# p2-001.net
KiCad netlist of a schematic drawn in EAGLE
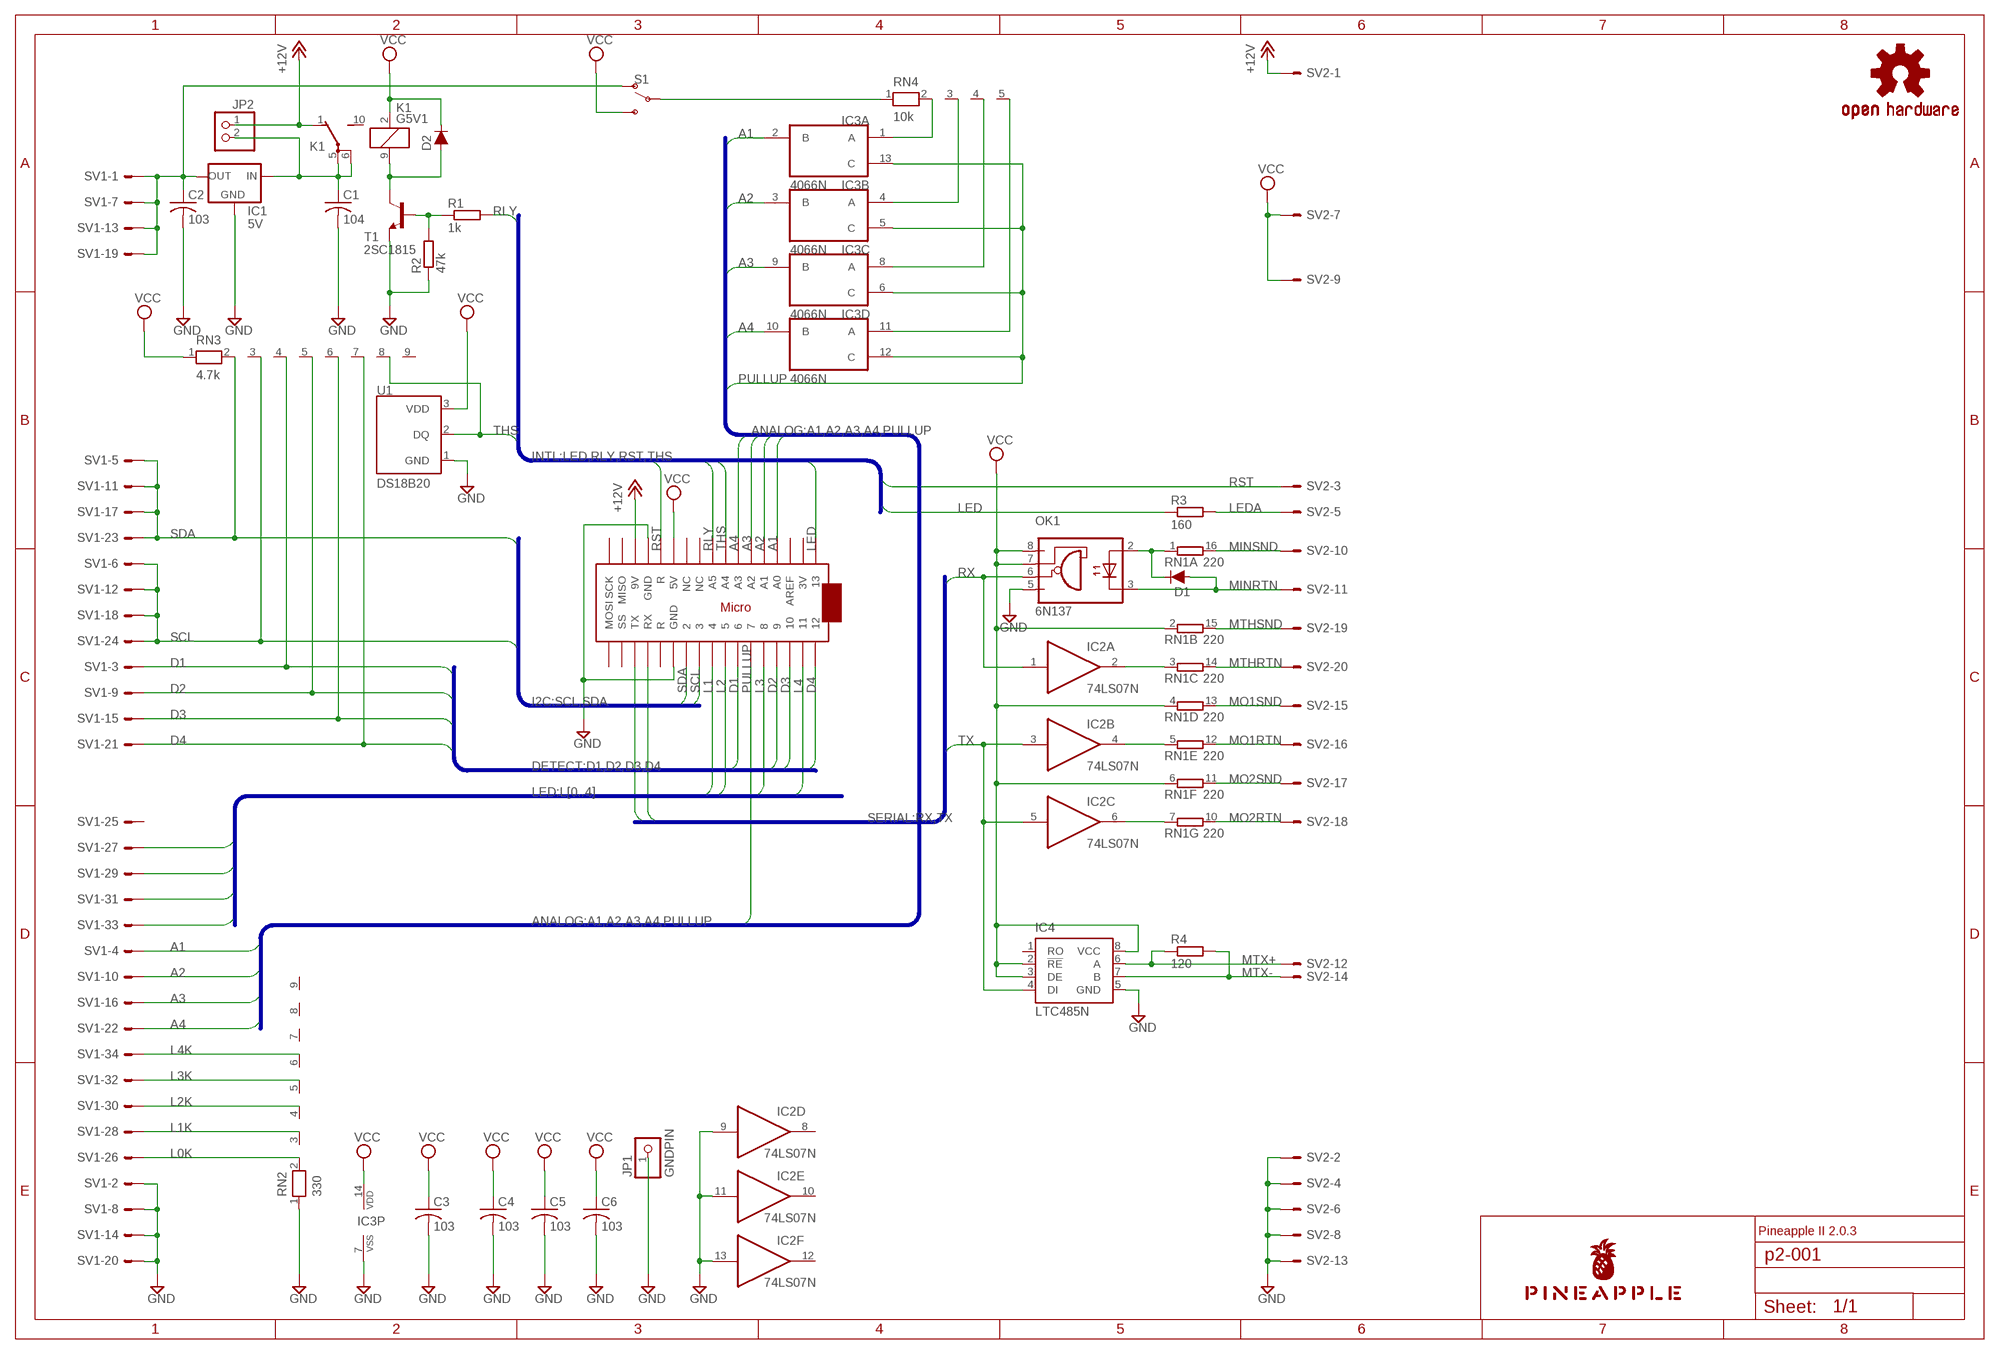
[diagram p0: schematic, sheet 1]

(export (version "E")
  (design (tool "Eeschema 10.0.6"))
  (components
    (comp (ref "C1")
      (value "104")
      (footprint "eagle-import:C025-025X050")
      (libsource (lib "eagle-import") (part "C-US025-025X050"))
    )
    (comp (ref "C2")
      (value "103")
      (footprint "eagle-import:C025-025X050")
      (libsource (lib "eagle-import") (part "C-US025-025X050"))
    )
    (comp (ref "C3")
      (value "103")
      (footprint "eagle-import:C025-025X050")
      (libsource (lib "eagle-import") (part "C-US025-025X050"))
    )
    (comp (ref "C4")
      (value "103")
      (footprint "eagle-import:C025-025X050")
      (libsource (lib "eagle-import") (part "C-US025-025X050"))
    )
    (comp (ref "C5")
      (value "103")
      (footprint "eagle-import:C025-025X050")
      (libsource (lib "eagle-import") (part "C-US025-025X050"))
    )
    (comp (ref "C6")
      (value "103")
      (footprint "eagle-import:C025-025X050")
      (libsource (lib "eagle-import") (part "C-US025-025X050"))
    )
    (comp (ref "D1")
      (value "DIODE-1N4148")
      (footprint "eagle-import:DIODE-1N4148")
      (libsource (lib "eagle-import") (part "DIODE-1N4148"))
    )
    (comp (ref "D2")
      (value "DIODE-1N4148")
      (footprint "eagle-import:DIODE-1N4148")
      (libsource (lib "eagle-import") (part "DIODE-1N4148"))
    )
    (comp (ref "IC1")
      (value "5V")
      (footprint "eagle-import:78XXL")
      (libsource (lib "eagle-import") (part "78XXL"))
    )
    (comp (ref "IC2")
      (value "74LS07N")
      (footprint "eagle-import:DIL14")
      (libsource (lib "eagle-import") (part "7407NLS"))
    )
    (comp (ref "IC3")
      (value "4066N")
      (footprint "eagle-import:DIL14")
      (libsource (lib "eagle-import") (part "4066N"))
    )
    (comp (ref "IC4")
      (value "LTC485N")
      (footprint "eagle-import:DIL08")
      (libsource (lib "eagle-import") (part "LTC485N"))
    )
    (comp (ref "JP1")
      (value "GNDPIN")
      (footprint "eagle-import:1X01")
      (libsource (lib "eagle-import") (part "PINHD-1X1"))
    )
    (comp (ref "JP2")
      (value "PINHD-1X2")
      (footprint "eagle-import:1X02")
      (libsource (lib "eagle-import") (part "PINHD-1X2"))
    )
    (comp (ref "K1")
      (value "G5V1")
      (footprint "eagle-import:G5V1")
      (fields (field (name "MPN") "G5V-1-DC24"))
      (libsource (lib "eagle-import") (part "G5V1"))
    )
    (comp (ref "LOGO1")
      (value "OSHW-LOGOS-COPPER")
      (footprint "eagle-import:OSHW-LOGO-S_COPPER")
      (libsource (lib "eagle-import") (part "OSHW-LOGOS-COPPER"))
    )
    (comp (ref "MC1")
      (value "ARDUINOMICRO")
      (footprint "eagle-import:ARDUINOMICRO")
      (libsource (lib "eagle-import") (part "ARDUINOMICRO"))
    )
    (comp (ref "OK1")
      (value "6N137")
      (footprint "eagle-import:DIL08")
      (libsource (lib "eagle-import") (part "6N137"))
    )
    (comp (ref "R1")
      (value "1k")
      (footprint "eagle-import:0204_5")
      (libsource (lib "eagle-import") (part "R-EU_0204/5"))
    )
    (comp (ref "R2")
      (value "47k")
      (footprint "eagle-import:0204_5")
      (libsource (lib "eagle-import") (part "R-EU_0204/5"))
    )
    (comp (ref "R3")
      (value "160")
      (footprint "eagle-import:0204_5")
      (libsource (lib "eagle-import") (part "R-EU_0204/5"))
    )
    (comp (ref "R4")
      (value "120")
      (footprint "eagle-import:0204_5")
      (libsource (lib "eagle-import") (part "R-EU_0204/5"))
    )
    (comp (ref "RN1")
      (value "220")
      (footprint "eagle-import:DIL16")
      (libsource (lib "eagle-import") (part "8R-N"))
    )
    (comp (ref "RN2")
      (value "330")
      (footprint "eagle-import:RN-9")
      (libsource (lib "eagle-import") (part "RN08"))
    )
    (comp (ref "RN3")
      (value "4.7k")
      (footprint "eagle-import:RN-9")
      (libsource (lib "eagle-import") (part "RN08"))
    )
    (comp (ref "RN4")
      (value "10k")
      (footprint "eagle-import:RN-5")
      (libsource (lib "eagle-import") (part "RN04"))
    )
    (comp (ref "S1")
      (value "SWITCH-SPDT-PTH-11.6X4.0MM")
      (footprint "eagle-import:SWITCH_SPDT_PTH_11.6X4.0MM")
      (libsource (lib "eagle-import") (part "SWITCH-SPDT-PTH-11.6X4.0MM"))
    )
    (comp (ref "SV1")
      (value "ML34LE")
      (footprint "eagle-import:ML34L")
      (libsource (lib "eagle-import") (part "ML34LE"))
    )
    (comp (ref "SV2")
      (value "ML20LE")
      (footprint "eagle-import:ML20L")
      (libsource (lib "eagle-import") (part "ML20LE"))
    )
    (comp (ref "T1")
      (value "2SC1815")
      (footprint "eagle-import:TO92-ECB")
      (libsource (lib "eagle-import") (part "2SC1815"))
    )
    (comp (ref "U$1")
      (value "PINEAPPLE450_SILK")
      (footprint "eagle-import:PINEAPPLE450_SILK")
      (libsource (lib "eagle-import") (part "PINEAPPLE450_SILK"))
    )
    (comp (ref "U1")
      (value "DS18B20")
      (footprint "eagle-import:TO-92-AMMO")
      (libsource (lib "eagle-import") (part "DS18B20"))
    )
  )
  (nets
    (net (code "11") (name "+12V") (class "Default")
      (node (ref "JP2") (pin "1") (pinfunction "1_1") (pintype "passive"))
      (node (ref "K1") (pin "1") (pinfunction "O_1") (pintype "passive"))
      (node (ref "MC1") (pin "P$20") (pinfunction "9V_P$20") (pintype "bidirectional"))
      (node (ref "SV2") (pin "1") (pinfunction "S_1") (pintype "passive"))
    )
    (net (code "12") (name "/A1") (class "Default")
      (node (ref "IC3") (pin "2") (pinfunction "B_2") (pintype "tri_state"))
      (node (ref "MC1") (pin "P$31") (pinfunction "A0_P$31") (pintype "bidirectional"))
      (node (ref "SV1") (pin "4") (pinfunction "S_4") (pintype "passive"))
    )
    (net (code "13") (name "/A2") (class "Default")
      (node (ref "IC3") (pin "3") (pinfunction "B_3") (pintype "tri_state"))
      (node (ref "MC1") (pin "P$30") (pinfunction "A1_P$30") (pintype "bidirectional"))
      (node (ref "SV1") (pin "10") (pinfunction "S_10") (pintype "passive"))
    )
    (net (code "14") (name "/A3") (class "Default")
      (node (ref "IC3") (pin "9") (pinfunction "B_9") (pintype "tri_state"))
      (node (ref "MC1") (pin "P$29") (pinfunction "A2_P$29") (pintype "bidirectional"))
      (node (ref "SV1") (pin "16") (pinfunction "S_16") (pintype "passive"))
    )
    (net (code "15") (name "/A4") (class "Default")
      (node (ref "IC3") (pin "10") (pinfunction "B_10") (pintype "tri_state"))
      (node (ref "MC1") (pin "P$28") (pinfunction "A3_P$28") (pintype "bidirectional"))
      (node (ref "SV1") (pin "22") (pinfunction "S_22") (pintype "passive"))
    )
    (net (code "16") (name "/D1") (class "Default")
      (node (ref "MC1") (pin "P$7") (pinfunction "6_P$7") (pintype "bidirectional"))
      (node (ref "RN3") (pin "4") (pinfunction "4_4") (pintype "passive"))
      (node (ref "SV1") (pin "3") (pinfunction "S_3") (pintype "passive"))
    )
    (net (code "17") (name "/D2") (class "Default")
      (node (ref "MC1") (pin "P$4") (pinfunction "9_P$4") (pintype "bidirectional"))
      (node (ref "RN3") (pin "5") (pinfunction "5_5") (pintype "passive"))
      (node (ref "SV1") (pin "9") (pinfunction "S_9") (pintype "passive"))
    )
    (net (code "18") (name "/D3") (class "Default")
      (node (ref "MC1") (pin "P$3") (pinfunction "10_P$3") (pintype "bidirectional"))
      (node (ref "RN3") (pin "6") (pinfunction "6_6") (pintype "passive"))
      (node (ref "SV1") (pin "15") (pinfunction "S_15") (pintype "passive"))
    )
    (net (code "19") (name "/D4") (class "Default")
      (node (ref "MC1") (pin "P$1") (pinfunction "12_P$1") (pintype "bidirectional"))
      (node (ref "RN3") (pin "7") (pinfunction "7_7") (pintype "passive"))
      (node (ref "SV1") (pin "21") (pinfunction "S_21") (pintype "passive"))
    )
    (net (code "20") (name "/L0K") (class "Default")
      (node (ref "RN2") (pin "2") (pinfunction "2_2") (pintype "passive"))
      (node (ref "SV1") (pin "26") (pinfunction "S_26") (pintype "passive"))
    )
    (net (code "21") (name "/L1") (class "Default")
      (node (ref "MC1") (pin "P$9") (pinfunction "4_P$9") (pintype "bidirectional"))
      (node (ref "SV1") (pin "27") (pinfunction "S_27") (pintype "passive"))
    )
    (net (code "22") (name "/L1K") (class "Default")
      (node (ref "RN2") (pin "3") (pinfunction "3_3") (pintype "passive"))
      (node (ref "SV1") (pin "28") (pinfunction "S_28") (pintype "passive"))
    )
    (net (code "23") (name "/L2") (class "Default")
      (node (ref "MC1") (pin "P$8") (pinfunction "5_P$8") (pintype "bidirectional"))
      (node (ref "SV1") (pin "29") (pinfunction "S_29") (pintype "passive"))
    )
    (net (code "24") (name "/L2K") (class "Default")
      (node (ref "RN2") (pin "4") (pinfunction "4_4") (pintype "passive"))
      (node (ref "SV1") (pin "30") (pinfunction "S_30") (pintype "passive"))
    )
    (net (code "25") (name "/L3") (class "Default")
      (node (ref "MC1") (pin "P$5") (pinfunction "8_P$5") (pintype "bidirectional"))
      (node (ref "SV1") (pin "31") (pinfunction "S_31") (pintype "passive"))
    )
    (net (code "26") (name "/L3K") (class "Default")
      (node (ref "RN2") (pin "5") (pinfunction "5_5") (pintype "passive"))
      (node (ref "SV1") (pin "32") (pinfunction "S_32") (pintype "passive"))
    )
    (net (code "27") (name "/L4") (class "Default")
      (node (ref "MC1") (pin "P$2") (pinfunction "11_P$2") (pintype "bidirectional"))
      (node (ref "SV1") (pin "33") (pinfunction "S_33") (pintype "passive"))
    )
    (net (code "28") (name "/L4K") (class "Default")
      (node (ref "RN2") (pin "6") (pinfunction "6_6") (pintype "passive"))
      (node (ref "SV1") (pin "34") (pinfunction "S_34") (pintype "passive"))
    )
    (net (code "29") (name "/LED") (class "Default")
      (node (ref "MC1") (pin "P$34") (pinfunction "13_P$34") (pintype "bidirectional"))
      (node (ref "R3") (pin "1") (pinfunction "1_1") (pintype "passive"))
    )
    (net (code "31") (name "/LEDA") (class "Default")
      (node (ref "R3") (pin "2") (pinfunction "2_2") (pintype "passive"))
      (node (ref "SV2") (pin "5") (pinfunction "S_5") (pintype "passive"))
    )
    (net (code "32") (name "/MINRTN") (class "Default")
      (node (ref "D1") (pin "A") (pinfunction "A_A") (pintype "passive"))
      (node (ref "OK1") (pin "3") (pinfunction "C_3") (pintype "passive"))
      (node (ref "SV2") (pin "11") (pinfunction "S_11") (pintype "passive"))
    )
    (net (code "33") (name "/MINSND") (class "Default")
      (node (ref "RN1") (pin "16") (pinfunction "2_16") (pintype "passive"))
      (node (ref "SV2") (pin "10") (pinfunction "S_10") (pintype "passive"))
    )
    (net (code "34") (name "/MO1RTN") (class "Default")
      (node (ref "RN1") (pin "12") (pinfunction "2_12") (pintype "passive"))
      (node (ref "SV2") (pin "16") (pinfunction "S_16") (pintype "passive"))
    )
    (net (code "35") (name "/MO1SND") (class "Default")
      (node (ref "RN1") (pin "13") (pinfunction "2_13") (pintype "passive"))
      (node (ref "SV2") (pin "15") (pinfunction "S_15") (pintype "passive"))
    )
    (net (code "36") (name "/MO2RTN") (class "Default")
      (node (ref "RN1") (pin "10") (pinfunction "2_10") (pintype "passive"))
      (node (ref "SV2") (pin "18") (pinfunction "S_18") (pintype "passive"))
    )
    (net (code "37") (name "/MO2SND") (class "Default")
      (node (ref "RN1") (pin "11") (pinfunction "2_11") (pintype "passive"))
      (node (ref "SV2") (pin "17") (pinfunction "S_17") (pintype "passive"))
    )
    (net (code "38") (name "/MTHRTN") (class "Default")
      (node (ref "RN1") (pin "14") (pinfunction "2_14") (pintype "passive"))
      (node (ref "SV2") (pin "20") (pinfunction "S_20") (pintype "passive"))
    )
    (net (code "39") (name "/MTHSND") (class "Default")
      (node (ref "RN1") (pin "15") (pinfunction "2_15") (pintype "passive"))
      (node (ref "SV2") (pin "19") (pinfunction "S_19") (pintype "passive"))
    )
    (net (code "40") (name "/MTX+") (class "Default")
      (node (ref "IC4") (pin "6") (pinfunction "A_6") (pintype "bidirectional"))
      (node (ref "R4") (pin "1") (pinfunction "1_1") (pintype "passive"))
      (node (ref "SV2") (pin "12") (pinfunction "S_12") (pintype "passive"))
    )
    (net (code "41") (name "/MTX-") (class "Default")
      (node (ref "IC4") (pin "7") (pinfunction "B_7") (pintype "bidirectional"))
      (node (ref "R4") (pin "2") (pinfunction "2_2") (pintype "passive"))
      (node (ref "SV2") (pin "14") (pinfunction "S_14") (pintype "passive"))
    )
    (net (code "42") (name "/PULLUP") (class "Default")
      (node (ref "IC3") (pin "12") (pinfunction "C_12") (pintype "input"))
      (node (ref "IC3") (pin "13") (pinfunction "C_13") (pintype "input"))
      (node (ref "IC3") (pin "5") (pinfunction "C_5") (pintype "input"))
      (node (ref "IC3") (pin "6") (pinfunction "C_6") (pintype "input"))
      (node (ref "MC1") (pin "P$6") (pinfunction "7_P$6") (pintype "bidirectional"))
    )
    (net (code "43") (name "/RLY") (class "Default")
      (node (ref "MC1") (pin "P$26") (pinfunction "A5_P$26") (pintype "bidirectional"))
      (node (ref "R1") (pin "2") (pinfunction "2_2") (pintype "passive"))
    )
    (net (code "44") (name "/RST") (class "Default")
      (node (ref "MC1") (pin "P$13") (pinfunction "R_P$13") (pintype "bidirectional"))
      (node (ref "SV2") (pin "3") (pinfunction "S_3") (pintype "passive"))
    )
    (net (code "45") (name "/RX") (class "Default")
      (node (ref "IC2") (pin "1") (pinfunction "I_1") (pintype "input"))
      (node (ref "MC1") (pin "P$14") (pinfunction "RX_P$14") (pintype "bidirectional"))
      (node (ref "OK1") (pin "6") (pinfunction "VO_6") (pintype "passive"))
    )
    (net (code "46") (name "/SCL") (class "Default")
      (node (ref "MC1") (pin "P$10") (pinfunction "3_P$10") (pintype "bidirectional"))
      (node (ref "RN3") (pin "3") (pinfunction "3_3") (pintype "passive"))
      (node (ref "SV1") (pin "12") (pinfunction "S_12") (pintype "passive"))
      (node (ref "SV1") (pin "18") (pinfunction "S_18") (pintype "passive"))
      (node (ref "SV1") (pin "24") (pinfunction "S_24") (pintype "passive"))
      (node (ref "SV1") (pin "6") (pinfunction "S_6") (pintype "passive"))
    )
    (net (code "47") (name "/SDA") (class "Default")
      (node (ref "MC1") (pin "P$11") (pinfunction "2_P$11") (pintype "bidirectional"))
      (node (ref "RN3") (pin "2") (pinfunction "2_2") (pintype "passive"))
      (node (ref "SV1") (pin "11") (pinfunction "S_11") (pintype "passive"))
      (node (ref "SV1") (pin "17") (pinfunction "S_17") (pintype "passive"))
      (node (ref "SV1") (pin "23") (pinfunction "S_23") (pintype "passive"))
      (node (ref "SV1") (pin "5") (pinfunction "S_5") (pintype "passive"))
    )
    (net (code "48") (name "/THS") (class "Default")
      (node (ref "MC1") (pin "P$27") (pinfunction "A4_P$27") (pintype "bidirectional"))
      (node (ref "RN3") (pin "8") (pinfunction "8_8") (pintype "passive"))
      (node (ref "U1") (pin "2") (pinfunction "DQ_2") (pintype "bidirectional"))
    )
    (net (code "49") (name "/TX") (class "Default")
      (node (ref "IC2") (pin "3") (pinfunction "I_3") (pintype "input"))
      (node (ref "IC2") (pin "5") (pinfunction "I_5") (pintype "input"))
      (node (ref "IC4") (pin "4") (pinfunction "DI_4") (pintype "input"))
      (node (ref "MC1") (pin "P$15") (pinfunction "TX_P$15") (pintype "bidirectional"))
    )
    (net (code "55") (name "GND") (class "Default")
      (node (ref "C1") (pin "2") (pinfunction "2_2") (pintype "passive"))
      (node (ref "C2") (pin "2") (pinfunction "2_2") (pintype "passive"))
      (node (ref "C3") (pin "2") (pinfunction "2_2") (pintype "passive"))
      (node (ref "C4") (pin "2") (pinfunction "2_2") (pintype "passive"))
      (node (ref "C5") (pin "2") (pinfunction "2_2") (pintype "passive"))
      (node (ref "C6") (pin "2") (pinfunction "2_2") (pintype "passive"))
      (node (ref "IC1") (pin "GND") (pinfunction "GND_GND") (pintype "input"))
      (node (ref "IC2") (pin "11") (pinfunction "I_11") (pintype "input"))
      (node (ref "IC2") (pin "13") (pinfunction "I_13") (pintype "input"))
      (node (ref "IC2") (pin "9") (pinfunction "I_9") (pintype "input"))
      (node (ref "IC3") (pin "7") (pinfunction "VSS_7") (pintype "power_in"))
      (node (ref "IC4") (pin "5") (pinfunction "GND_5") (pintype "input"))
      (node (ref "JP1") (pin "1") (pinfunction "1_1") (pintype "passive"))
      (node (ref "MC1") (pin "P$12") (pinfunction "GND_P$12") (pintype "bidirectional"))
      (node (ref "MC1") (pin "P$21") (pinfunction "GND_P$21") (pintype "bidirectional"))
      (node (ref "OK1") (pin "5") (pinfunction "GND_5") (pintype "passive"))
      (node (ref "R2") (pin "1") (pinfunction "1_1") (pintype "passive"))
      (node (ref "RN2") (pin "1") (pinfunction "1_1") (pintype "passive"))
      (node (ref "SV1") (pin "14") (pinfunction "S_14") (pintype "passive"))
      (node (ref "SV1") (pin "2") (pinfunction "S_2") (pintype "passive"))
      (node (ref "SV1") (pin "20") (pinfunction "S_20") (pintype "passive"))
      (node (ref "SV1") (pin "8") (pinfunction "S_8") (pintype "passive"))
      (node (ref "SV2") (pin "13") (pinfunction "S_13") (pintype "passive"))
      (node (ref "SV2") (pin "2") (pinfunction "S_2") (pintype "passive"))
      (node (ref "SV2") (pin "4") (pinfunction "S_4") (pintype "passive"))
      (node (ref "SV2") (pin "6") (pinfunction "S_6") (pintype "passive"))
      (node (ref "SV2") (pin "8") (pinfunction "S_8") (pintype "passive"))
      (node (ref "T1") (pin "E") (pinfunction "E_E") (pintype "passive"))
      (node (ref "U1") (pin "1") (pinfunction "GND_1") (pintype "power_in"))
    )
    (net (code "56") (name "Net-(C1-Pad1)") (class "Default")
      (node (ref "C1") (pin "1") (pinfunction "1_1") (pintype "passive"))
      (node (ref "IC1") (pin "IN") (pinfunction "IN_IN") (pintype "input"))
      (node (ref "JP2") (pin "2") (pinfunction "2_2") (pintype "passive"))
      (node (ref "K1") (pin "5") (pinfunction "P_5") (pintype "passive"))
      (node (ref "K1") (pin "6") (pinfunction "P_6") (pintype "passive"))
    )
    (net (code "57") (name "Net-(IC2A-O)") (class "Default")
      (node (ref "IC2") (pin "2") (pinfunction "O_2") (pintype "open_collector"))
      (node (ref "RN1") (pin "3") (pinfunction "1_3") (pintype "passive"))
    )
    (net (code "58") (name "Net-(IC2B-O)") (class "Default")
      (node (ref "IC2") (pin "4") (pinfunction "O_4") (pintype "open_collector"))
      (node (ref "RN1") (pin "5") (pinfunction "1_5") (pintype "passive"))
    )
    (net (code "59") (name "Net-(IC2C-O)") (class "Default")
      (node (ref "IC2") (pin "6") (pinfunction "O_6") (pintype "open_collector"))
      (node (ref "RN1") (pin "7") (pinfunction "1_7") (pintype "passive"))
    )
    (net (code "60") (name "Net-(IC3A-A)") (class "Default")
      (node (ref "IC3") (pin "1") (pinfunction "A_1") (pintype "tri_state"))
      (node (ref "RN4") (pin "2") (pinfunction "2_2") (pintype "passive"))
    )
    (net (code "61") (name "Net-(IC3B-A)") (class "Default")
      (node (ref "IC3") (pin "4") (pinfunction "A_4") (pintype "tri_state"))
      (node (ref "RN4") (pin "3") (pinfunction "3_3") (pintype "passive"))
    )
    (net (code "62") (name "Net-(IC3C-A)") (class "Default")
      (node (ref "IC3") (pin "8") (pinfunction "A_8") (pintype "tri_state"))
      (node (ref "RN4") (pin "4") (pinfunction "4_4") (pintype "passive"))
    )
    (net (code "63") (name "Net-(IC3D-A)") (class "Default")
      (node (ref "IC3") (pin "11") (pinfunction "A_11") (pintype "tri_state"))
      (node (ref "RN4") (pin "5") (pinfunction "5_5") (pintype "passive"))
    )
    (net (code "64") (name "Net-(K1A-2)") (class "Default")
      (node (ref "D2") (pin "A") (pinfunction "A_A") (pintype "passive"))
      (node (ref "K1") (pin "9") (pinfunction "2_9") (pintype "passive"))
      (node (ref "T1") (pin "C") (pinfunction "C_C") (pintype "passive"))
    )
    (net (code "65") (name "Net-(OK1-A)") (class "Default")
      (node (ref "D1") (pin "C") (pinfunction "C_C") (pintype "passive"))
      (node (ref "OK1") (pin "2") (pinfunction "A_2") (pintype "passive"))
      (node (ref "RN1") (pin "1") (pinfunction "1_1") (pintype "passive"))
    )
    (net (code "66") (name "Net-(R1-Pad1)") (class "Default")
      (node (ref "R1") (pin "1") (pinfunction "1_1") (pintype "passive"))
      (node (ref "R2") (pin "2") (pinfunction "2_2") (pintype "passive"))
      (node (ref "T1") (pin "B") (pinfunction "B_B") (pintype "passive"))
    )
    (net (code "67") (name "Net-(S1-O)") (class "Default")
      (node (ref "C2") (pin "1") (pinfunction "1_1") (pintype "passive"))
      (node (ref "IC1") (pin "OUT") (pinfunction "OUT_OUT") (pintype "passive"))
      (node (ref "S1") (pin "1") (pinfunction "O_1") (pintype "passive"))
      (node (ref "SV1") (pin "1") (pinfunction "S_1") (pintype "passive"))
      (node (ref "SV1") (pin "13") (pinfunction "S_13") (pintype "passive"))
      (node (ref "SV1") (pin "19") (pinfunction "S_19") (pintype "passive"))
      (node (ref "SV1") (pin "7") (pinfunction "S_7") (pintype "passive"))
    )
    (net (code "68") (name "Net-(S1-P)") (class "Default")
      (node (ref "RN4") (pin "1") (pinfunction "1_1") (pintype "passive"))
      (node (ref "S1") (pin "2") (pinfunction "P_2") (pintype "passive"))
    )
    (net (code "69") (name "VCC") (class "Default")
      (node (ref "C3") (pin "1") (pinfunction "1_1") (pintype "passive"))
      (node (ref "C4") (pin "1") (pinfunction "1_1") (pintype "passive"))
      (node (ref "C5") (pin "1") (pinfunction "1_1") (pintype "passive"))
      (node (ref "C6") (pin "1") (pinfunction "1_1") (pintype "passive"))
      (node (ref "D2") (pin "C") (pinfunction "C_C") (pintype "passive"))
      (node (ref "IC3") (pin "14") (pinfunction "VDD_14") (pintype "power_in"))
      (node (ref "IC4") (pin "2") (pinfunction "~{RE}_2") (pintype "input"))
      (node (ref "IC4") (pin "3") (pinfunction "DE_3") (pintype "input"))
      (node (ref "IC4") (pin "8") (pinfunction "VCC_8") (pintype "input"))
      (node (ref "K1") (pin "2") (pinfunction "1_2") (pintype "passive"))
      (node (ref "MC1") (pin "P$23") (pinfunction "5V_P$23") (pintype "bidirectional"))
      (node (ref "OK1") (pin "7") (pinfunction "VE_7") (pintype "passive"))
      (node (ref "OK1") (pin "8") (pinfunction "VCC_8") (pintype "passive"))
      (node (ref "RN1") (pin "2") (pinfunction "1_2") (pintype "passive"))
      (node (ref "RN1") (pin "4") (pinfunction "1_4") (pintype "passive"))
      (node (ref "RN1") (pin "6") (pinfunction "1_6") (pintype "passive"))
      (node (ref "RN3") (pin "1") (pinfunction "1_1") (pintype "passive"))
      (node (ref "S1") (pin "3") (pinfunction "S_3") (pintype "passive"))
      (node (ref "SV2") (pin "7") (pinfunction "S_7") (pintype "passive"))
      (node (ref "SV2") (pin "9") (pinfunction "S_9") (pintype "passive"))
      (node (ref "U1") (pin "3") (pinfunction "VDD_3") (pintype "power_in"))
    )
    (net (code "70") (name "unconnected-(IC2D-O-Pad8)") (class "Default")
      (node (ref "IC2") (pin "8") (pinfunction "O_8") (pintype "open_collector"))
    )
    (net (code "71") (name "unconnected-(IC2E-O-Pad10)") (class "Default")
      (node (ref "IC2") (pin "10") (pinfunction "O_10") (pintype "open_collector"))
    )
    (net (code "72") (name "unconnected-(IC2F-O-Pad12)") (class "Default")
      (node (ref "IC2") (pin "12") (pinfunction "O_12") (pintype "open_collector"))
    )
    (net (code "73") (name "unconnected-(IC4-RO-Pad1)") (class "Default")
      (node (ref "IC4") (pin "1") (pinfunction "RO_1") (pintype "output"))
    )
    (net (code "74") (name "unconnected-(K1B-S-Pad10)") (class "Default")
      (node (ref "K1") (pin "10") (pinfunction "S_10") (pintype "passive"))
    )
    (net (code "75") (name "unconnected-(MC1-3V-PadP$33)") (class "Default")
      (node (ref "MC1") (pin "P$33") (pinfunction "3V_P$33") (pintype "bidirectional"))
    )
    (net (code "76") (name "unconnected-(MC1-AREF-PadP$32)") (class "Default")
      (node (ref "MC1") (pin "P$32") (pinfunction "AREF_P$32") (pintype "bidirectional"))
    )
    (net (code "77") (name "unconnected-(MC1-MISO-PadP$19)") (class "Default")
      (node (ref "MC1") (pin "P$19") (pinfunction "MISO_P$19") (pintype "bidirectional"))
    )
    (net (code "78") (name "unconnected-(MC1-MOSI-PadP$17)") (class "Default")
      (node (ref "MC1") (pin "P$17") (pinfunction "MOSI_P$17") (pintype "bidirectional"))
    )
    (net (code "79") (name "unconnected-(MC1-NC-PadP$24)") (class "Default")
      (node (ref "MC1") (pin "P$24") (pinfunction "NC_P$24") (pintype "bidirectional"))
    )
    (net (code "80") (name "unconnected-(MC1-NC-PadP$25)") (class "Default")
      (node (ref "MC1") (pin "P$25") (pinfunction "NC_P$25") (pintype "bidirectional"))
    )
    (net (code "81") (name "unconnected-(MC1-R-PadP$22)") (class "Default")
      (node (ref "MC1") (pin "P$22") (pinfunction "R_P$22") (pintype "bidirectional"))
    )
    (net (code "82") (name "unconnected-(MC1-SCK-PadP$18)") (class "Default")
      (node (ref "MC1") (pin "P$18") (pinfunction "SCK_P$18") (pintype "bidirectional"))
    )
    (net (code "83") (name "unconnected-(MC1-SS-PadP$16)") (class "Default")
      (node (ref "MC1") (pin "P$16") (pinfunction "SS_P$16") (pintype "bidirectional"))
    )
    (net (code "84") (name "unconnected-(RN2-Pad7)") (class "Default")
      (node (ref "RN2") (pin "7") (pinfunction "7_7") (pintype "passive"))
    )
    (net (code "85") (name "unconnected-(RN2-Pad8)") (class "Default")
      (node (ref "RN2") (pin "8") (pinfunction "8_8") (pintype "passive"))
    )
    (net (code "86") (name "unconnected-(RN2-Pad9)") (class "Default")
      (node (ref "RN2") (pin "9") (pinfunction "9_9") (pintype "passive"))
    )
    (net (code "87") (name "unconnected-(RN3-Pad9)") (class "Default")
      (node (ref "RN3") (pin "9") (pinfunction "9_9") (pintype "passive"))
    )
    (net (code "88") (name "unconnected-(SV1R-S-Pad25)") (class "Default")
      (node (ref "SV1") (pin "25") (pinfunction "S_25") (pintype "passive"))
    )
  )
)
